# PCB_sch.net
KiCad netlist of a schematic drawn in EAGLE
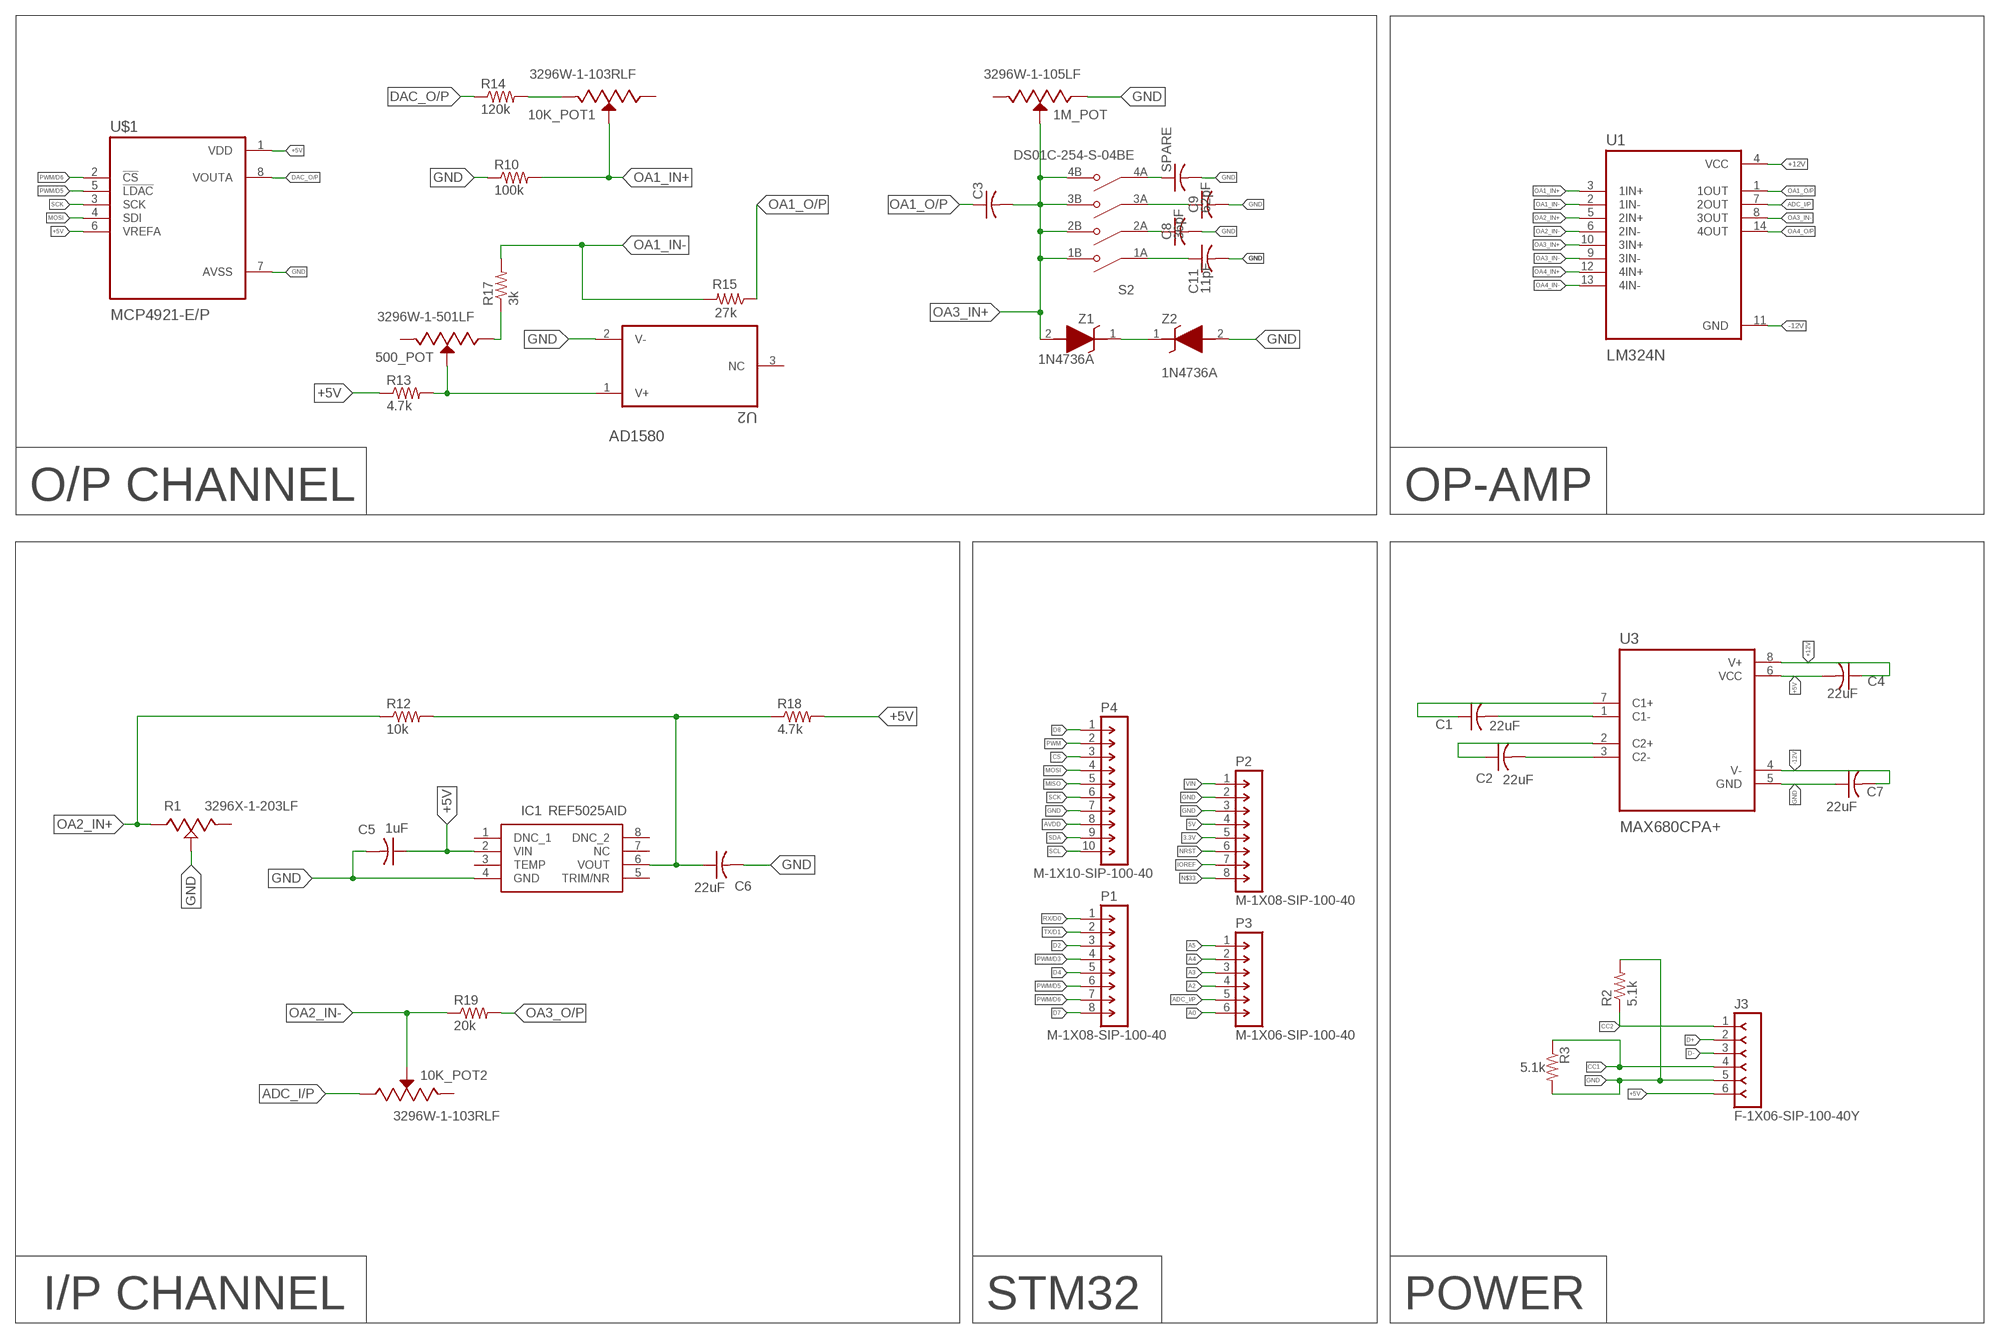
[diagram p0: schematic, sheet 1]

(export (version "E")
  (design (tool "Eeschema 10.0.6"))
  (components
    (comp (ref "1M_POT")
      (value "3296W-1-105LF")
      (footprint "eagle-import:TRIM_3296W-1-105LF")
      (fields (field (name "MF") "Bourns"))
      (libsource (lib "eagle-import") (part "3296W-1-105LF"))
    )
    (comp (ref "10K_POT1")
      (value "3296W-1-103RLF")
      (footprint "eagle-import:TRIM_3296W-1-103RLF")
      (fields (field (name "MF") "Bourns"))
      (libsource (lib "eagle-import") (part "3296W-1-103RLF"))
    )
    (comp (ref "10K_POT2")
      (value "3296W-1-103RLF")
      (footprint "eagle-import:TRIM_3296W-1-103RLF")
      (fields (field (name "MF") "Bourns"))
      (libsource (lib "eagle-import") (part "3296W-1-103RLF"))
    )
    (comp (ref "500_POT")
      (value "3296W-1-501LF")
      (footprint "eagle-import:TRIM_3296W-1-501LF")
      (fields (field (name "MF") "Bourns"))
      (libsource (lib "eagle-import") (part "3296W-1-501LF"))
    )
    (comp (ref "C1")
      (value "22uF")
      (footprint "eagle-import:C0805")
      (libsource (lib "eagle-import") (part "C-USC0805"))
    )
    (comp (ref "C2")
      (value "22uF")
      (footprint "eagle-import:C0805")
      (libsource (lib "eagle-import") (part "C-USC0805"))
    )
    (comp (ref "C3")
      (value "C-US050-030X075")
      (footprint "eagle-import:C050-030X075")
      (libsource (lib "eagle-import") (part "C-US050-030X075"))
    )
    (comp (ref "C4")
      (value "22uF")
      (footprint "eagle-import:C0805")
      (libsource (lib "eagle-import") (part "C-USC0805"))
    )
    (comp (ref "C5")
      (value "1uF")
      (footprint "eagle-import:C0805K")
      (libsource (lib "eagle-import") (part "C-USC0805K"))
    )
    (comp (ref "C6")
      (value "22uF")
      (footprint "eagle-import:C0805K")
      (libsource (lib "eagle-import") (part "C-USC0805K"))
    )
    (comp (ref "C7")
      (value "22uF")
      (footprint "eagle-import:C0805")
      (libsource (lib "eagle-import") (part "C-USC0805"))
    )
    (comp (ref "C8")
      (value "36pF")
      (footprint "eagle-import:C0805")
      (libsource (lib "eagle-import") (part "C-USC0805"))
    )
    (comp (ref "C9")
      (value "62pF")
      (footprint "eagle-import:C0805")
      (libsource (lib "eagle-import") (part "C-USC0805"))
    )
    (comp (ref "C11")
      (value "11pF")
      (footprint "eagle-import:C0805")
      (fields (field (name "SPICEPREFIX") "C"))
      (libsource (lib "eagle-import") (part "C-USC0805"))
    )
    (comp (ref "IC1")
      (value "REF5025AID")
      (footprint "eagle-import:SOIC127P600X175-8N")
      (fields (field (name "MOUSER_PART_NUMBER") "595-REF5025AID"))
      (libsource (lib "eagle-import") (part "REF5025AID"))
    )
    (comp (ref "J3")
      (value "F-1X06-SIP-100-40Y")
      (footprint "eagle-import:SIP-100-06-40Y")
      (libsource (lib "eagle-import") (part "F-1X06-SIP-100-40Y"))
    )
    (comp (ref "P1")
      (value "M-1X08-SIP-100-40")
      (footprint "eagle-import:SIP-100-08-40")
      (libsource (lib "eagle-import") (part "M-1X08-SIP-100-40"))
    )
    (comp (ref "P2")
      (value "M-1X08-SIP-100-40")
      (footprint "eagle-import:SIP-100-08-40")
      (libsource (lib "eagle-import") (part "M-1X08-SIP-100-40"))
    )
    (comp (ref "P3")
      (value "M-1X06-SIP-100-40")
      (footprint "eagle-import:SIP-100-06-40")
      (libsource (lib "eagle-import") (part "M-1X06-SIP-100-40"))
    )
    (comp (ref "P4")
      (value "M-1X10-SIP-100-40")
      (footprint "eagle-import:SIP-100-10-40")
      (libsource (lib "eagle-import") (part "M-1X10-SIP-100-40"))
    )
    (comp (ref "R1")
      (value "3296X-1-203LF")
      (footprint "eagle-import:TRIM_3296X-1-203LF")
      (fields (field (name "MF") "Bourns"))
      (libsource (lib "eagle-import") (part "3296X-1-203LF"))
    )
    (comp (ref "R2")
      (value "5.1k")
      (footprint "eagle-import:R0805")
      (libsource (lib "eagle-import") (part "R-US_R0805"))
    )
    (comp (ref "R3")
      (value "5.1k")
      (footprint "eagle-import:R0805")
      (libsource (lib "eagle-import") (part "R-US_R0805"))
    )
    (comp (ref "R10")
      (value "100k")
      (footprint "eagle-import:M0805")
      (libsource (lib "eagle-import") (part "R-US_M0805"))
    )
    (comp (ref "R12")
      (value "10k")
      (footprint "eagle-import:M0805")
      (libsource (lib "eagle-import") (part "R-US_M0805"))
    )
    (comp (ref "R13")
      (value "4.7k")
      (footprint "eagle-import:M0805")
      (libsource (lib "eagle-import") (part "R-US_M0805"))
    )
    (comp (ref "R14")
      (value "120k")
      (footprint "eagle-import:M0805")
      (libsource (lib "eagle-import") (part "R-US_M0805"))
    )
    (comp (ref "R15")
      (value "27k")
      (footprint "eagle-import:M0805")
      (libsource (lib "eagle-import") (part "R-US_M0805"))
    )
    (comp (ref "R17")
      (value "3k")
      (footprint "eagle-import:M0805")
      (libsource (lib "eagle-import") (part "R-US_M0805"))
    )
    (comp (ref "R18")
      (value "4.7k")
      (footprint "eagle-import:M0805")
      (libsource (lib "eagle-import") (part "R-US_M0805"))
    )
    (comp (ref "R19")
      (value "20k")
      (footprint "eagle-import:M0805")
      (libsource (lib "eagle-import") (part "R-US_M0805"))
    )
    (comp (ref "S2")
      (value "DS01C-254-S-04BE")
      (footprint "eagle-import:SW_DS01C-254-S-04BE")
      (fields (field (name "MANUFACTURER") "CUI"))
      (libsource (lib "eagle-import") (part "DS01C-254-S-04BE"))
    )
    (comp (ref "SPARE")
      (value "C-USC0805")
      (footprint "eagle-import:C0805")
      (libsource (lib "eagle-import") (part "C-USC0805"))
    )
    (comp (ref "U$1")
      (value "MCP4921-E/P")
      (footprint "eagle-import:DIP787W46P254L927H533Q8")
      (fields (field (name "MF") "Microchip"))
      (libsource (lib "eagle-import") (part "MCP4921-E/P"))
    )
    (comp (ref "U1")
      (value "LM324N")
      (footprint "eagle-import:DIP794W45P254L1969H508Q14")
      (fields (field (name "MF") "STMicroelectronics"))
      (libsource (lib "eagle-import") (part "LM324N"))
    )
    (comp (ref "U2")
      (value "AD1580")
      (footprint "eagle-import:SOT96P237X112-3N")
      (libsource (lib "eagle-import") (part "AD1580BRTZ-R2-REEL7"))
    )
    (comp (ref "U3")
      (value "MAX680CPA+")
      (footprint "eagle-import:DIP794W47P254L991H457Q8")
      (fields (field (name "MF") "Maxim Integrated Products"))
      (libsource (lib "eagle-import") (part "MAX680CPA+"))
    )
    (comp (ref "Z1")
      (value "1N4736A")
      (footprint "eagle-import:DIOAD1413W86L463D238")
      (fields (field (name "MOUSER_PART_NUMBER") "512-1N4736A"))
      (libsource (lib "eagle-import") (part "1N4736A"))
    )
    (comp (ref "Z2")
      (value "1N4736A")
      (footprint "eagle-import:DIOAD1413W86L463D238")
      (fields (field (name "MOUSER_PART_NUMBER") "512-1N4736A"))
      (libsource (lib "eagle-import") (part "1N4736A"))
    )
  )
  (nets
    (net (code "1") (name "+5V") (class "Default")
      (node (ref "C4") (pin "2") (pinfunction "2_2") (pintype "passive"))
      (node (ref "C5") (pin "1") (pinfunction "1_1") (pintype "passive"))
      (node (ref "IC1") (pin "2") (pinfunction "VIN_2") (pintype "bidirectional"))
      (node (ref "J3") (pin "6") (pinfunction "6_6") (pintype "passive"))
      (node (ref "R13") (pin "1") (pinfunction "1_1") (pintype "passive"))
      (node (ref "R18") (pin "2") (pinfunction "2_2") (pintype "passive"))
      (node (ref "U$1") (pin "1") (pinfunction "VDD_1") (pintype "power_in"))
      (node (ref "U$1") (pin "6") (pinfunction "VREFA_6") (pintype "input"))
      (node (ref "U3") (pin "6") (pinfunction "VCC_6") (pintype "power_in"))
    )
    (net (code "2") (name "+12V") (class "Default")
      (node (ref "C4") (pin "1") (pinfunction "1_1") (pintype "passive"))
      (node (ref "U1") (pin "4") (pinfunction "VCC_4") (pintype "power_in"))
      (node (ref "U3") (pin "8") (pinfunction "V+_8") (pintype "power_in"))
    )
    (net (code "3") (name "-12V") (class "Default")
      (node (ref "C7") (pin "2") (pinfunction "2_2") (pintype "passive"))
      (node (ref "U1") (pin "11") (pinfunction "GND_11") (pintype "power_in"))
      (node (ref "U3") (pin "4") (pinfunction "V-_4") (pintype "power_in"))
    )
    (net (code "4") (name "3.3V") (class "Default")
      (node (ref "P2") (pin "5") (pinfunction "5_5") (pintype "passive"))
    )
    (net (code "5") (name "5V") (class "Default")
      (node (ref "P2") (pin "4") (pinfunction "4_4") (pintype "passive"))
    )
    (net (code "6") (name "A0") (class "Default")
      (node (ref "P3") (pin "6") (pinfunction "6_6") (pintype "passive"))
    )
    (net (code "7") (name "A2") (class "Default")
      (node (ref "P3") (pin "4") (pinfunction "4_4") (pintype "passive"))
    )
    (net (code "8") (name "A3") (class "Default")
      (node (ref "P3") (pin "3") (pinfunction "3_3") (pintype "passive"))
    )
    (net (code "9") (name "A4") (class "Default")
      (node (ref "P3") (pin "2") (pinfunction "2_2") (pintype "passive"))
    )
    (net (code "10") (name "A5") (class "Default")
      (node (ref "P3") (pin "1") (pinfunction "1_1") (pintype "passive"))
    )
    (net (code "11") (name "ADC_I{slash}P") (class "Default")
      (node (ref "10K_POT2") (pin "1") (pinfunction "CCW_1") (pintype "passive"))
      (node (ref "P3") (pin "5") (pinfunction "5_5") (pintype "passive"))
      (node (ref "U1") (pin "7") (pinfunction "2OUT_7") (pintype "output"))
    )
    (net (code "12") (name "AVDD") (class "Default")
      (node (ref "P4") (pin "8") (pinfunction "8_8") (pintype "passive"))
    )
    (net (code "13") (name "CC1") (class "Default")
      (node (ref "J3") (pin "4") (pinfunction "4_4") (pintype "passive"))
      (node (ref "R3") (pin "1") (pinfunction "1_1") (pintype "passive"))
    )
    (net (code "14") (name "CC2") (class "Default")
      (node (ref "J3") (pin "1") (pinfunction "1_1") (pintype "passive"))
      (node (ref "R2") (pin "1") (pinfunction "1_1") (pintype "passive"))
    )
    (net (code "15") (name "CS") (class "Default")
      (node (ref "P4") (pin "3") (pinfunction "3_3") (pintype "passive"))
    )
    (net (code "16") (name "D+") (class "Default")
      (node (ref "J3") (pin "2") (pinfunction "2_2") (pintype "passive"))
    )
    (net (code "17") (name "D-") (class "Default")
      (node (ref "J3") (pin "3") (pinfunction "3_3") (pintype "passive"))
    )
    (net (code "18") (name "D2") (class "Default")
      (node (ref "P1") (pin "3") (pinfunction "3_3") (pintype "passive"))
    )
    (net (code "19") (name "D4") (class "Default")
      (node (ref "P1") (pin "5") (pinfunction "5_5") (pintype "passive"))
    )
    (net (code "20") (name "D7") (class "Default")
      (node (ref "P1") (pin "8") (pinfunction "8_8") (pintype "passive"))
    )
    (net (code "21") (name "D8") (class "Default")
      (node (ref "P4") (pin "1") (pinfunction "1_1") (pintype "passive"))
    )
    (net (code "22") (name "DAC_O{slash}P") (class "Default")
      (node (ref "R14") (pin "1") (pinfunction "1_1") (pintype "passive"))
      (node (ref "U$1") (pin "8") (pinfunction "VOUTA_8") (pintype "output"))
    )
    (net (code "23") (name "GND") (class "Default")
      (node (ref "1M_POT") (pin "1") (pinfunction "CCW_1") (pintype "passive"))
      (node (ref "C11") (pin "2") (pinfunction "2_2") (pintype "passive"))
      (node (ref "C5") (pin "2") (pinfunction "2_2") (pintype "passive"))
      (node (ref "C6") (pin "2") (pinfunction "2_2") (pintype "passive"))
      (node (ref "C7") (pin "1") (pinfunction "1_1") (pintype "passive"))
      (node (ref "C8") (pin "2") (pinfunction "2_2") (pintype "passive"))
      (node (ref "C9") (pin "2") (pinfunction "2_2") (pintype "passive"))
      (node (ref "IC1") (pin "4") (pinfunction "GND_4") (pintype "bidirectional"))
      (node (ref "J3") (pin "5") (pinfunction "5_5") (pintype "passive"))
      (node (ref "P2") (pin "2") (pinfunction "2_2") (pintype "passive"))
      (node (ref "P2") (pin "3") (pinfunction "3_3") (pintype "passive"))
      (node (ref "P4") (pin "7") (pinfunction "7_7") (pintype "passive"))
      (node (ref "R1") (pin "2") (pinfunction "WIPER_2") (pintype "passive"))
      (node (ref "R10") (pin "1") (pinfunction "1_1") (pintype "passive"))
      (node (ref "R2") (pin "2") (pinfunction "2_2") (pintype "passive"))
      (node (ref "R3") (pin "2") (pinfunction "2_2") (pintype "passive"))
      (node (ref "SPARE") (pin "2") (pinfunction "2_2") (pintype "passive"))
      (node (ref "U$1") (pin "7") (pinfunction "AVSS_7") (pintype "power_in"))
      (node (ref "U2") (pin "2") (pinfunction "V-_2") (pintype "power_in"))
      (node (ref "U3") (pin "5") (pinfunction "GND_5") (pintype "power_in"))
      (node (ref "Z2") (pin "2") (pinfunction "A_2") (pintype "bidirectional"))
    )
    (net (code "24") (name "IOREF") (class "Default")
      (node (ref "P2") (pin "7") (pinfunction "7_7") (pintype "passive"))
    )
    (net (code "25") (name "MISO") (class "Default")
      (node (ref "P4") (pin "5") (pinfunction "5_5") (pintype "passive"))
    )
    (net (code "26") (name "MOSI") (class "Default")
      (node (ref "P4") (pin "4") (pinfunction "4_4") (pintype "passive"))
      (node (ref "U$1") (pin "4") (pinfunction "SDI_4") (pintype "input"))
    )
    (net (code "27") (name "N$33") (class "Default")
      (node (ref "P2") (pin "8") (pinfunction "8_8") (pintype "passive"))
    )
    (net (code "28") (name "NRST") (class "Default")
      (node (ref "P2") (pin "6") (pinfunction "6_6") (pintype "passive"))
    )
    (net (code "29") (name "Net-(10K_POT1-CW)") (class "Default")
      (node (ref "10K_POT1") (pin "3") (pinfunction "CW_3") (pintype "passive"))
      (node (ref "R14") (pin "2") (pinfunction "2_2") (pintype "passive"))
    )
    (net (code "30") (name "Net-(10K_POT1-WIPER)") (class "Default")
      (node (ref "10K_POT1") (pin "2") (pinfunction "WIPER_2") (pintype "passive"))
      (node (ref "R10") (pin "2") (pinfunction "2_2") (pintype "passive"))
    )
    (net (code "31") (name "Net-(500_POT-CCW)") (class "Default")
      (node (ref "500_POT") (pin "1") (pinfunction "CCW_1") (pintype "passive"))
      (node (ref "R17") (pin "1") (pinfunction "1_1") (pintype "passive"))
    )
    (net (code "32") (name "Net-(500_POT-WIPER)") (class "Default")
      (node (ref "500_POT") (pin "2") (pinfunction "WIPER_2") (pintype "passive"))
      (node (ref "R13") (pin "2") (pinfunction "2_2") (pintype "passive"))
      (node (ref "U2") (pin "1") (pinfunction "V+_1") (pintype "power_in"))
    )
    (net (code "33") (name "Net-(IC1-VOUT)") (class "Default")
      (node (ref "C6") (pin "1") (pinfunction "1_1") (pintype "passive"))
      (node (ref "IC1") (pin "6") (pinfunction "VOUT_6") (pintype "bidirectional"))
      (node (ref "R12") (pin "2") (pinfunction "2_2") (pintype "passive"))
      (node (ref "R18") (pin "1") (pinfunction "1_1") (pintype "passive"))
    )
    (net (code "34") (name "Net-(R15-Pad2)") (class "Default")
      (node (ref "R15") (pin "2") (pinfunction "2_2") (pintype "passive"))
      (node (ref "R17") (pin "2") (pinfunction "2_2") (pintype "passive"))
    )
    (net (code "35") (name "Net-(S2-COM1)") (class "Default")
      (node (ref "C11") (pin "1") (pinfunction "1_1") (pintype "passive"))
      (node (ref "S2") (pin "1A") (pinfunction "COM1_1A") (pintype "passive"))
    )
    (net (code "36") (name "Net-(S2-COM2)") (class "Default")
      (node (ref "C8") (pin "1") (pinfunction "1_1") (pintype "passive"))
      (node (ref "S2") (pin "2A") (pinfunction "COM2_2A") (pintype "passive"))
    )
    (net (code "37") (name "Net-(S2-COM3)") (class "Default")
      (node (ref "C9") (pin "1") (pinfunction "1_1") (pintype "passive"))
      (node (ref "S2") (pin "3A") (pinfunction "COM3_3A") (pintype "passive"))
    )
    (net (code "38") (name "Net-(S2-COM4)") (class "Default")
      (node (ref "S2") (pin "4A") (pinfunction "COM4_4A") (pintype "passive"))
      (node (ref "SPARE") (pin "1") (pinfunction "1_1") (pintype "passive"))
    )
    (net (code "39") (name "Net-(U3-C1+)") (class "Default")
      (node (ref "C1") (pin "1") (pinfunction "1_1") (pintype "passive"))
      (node (ref "U3") (pin "7") (pinfunction "C1+_7") (pintype "passive"))
    )
    (net (code "40") (name "Net-(U3-C1-)") (class "Default")
      (node (ref "C1") (pin "2") (pinfunction "2_2") (pintype "passive"))
      (node (ref "U3") (pin "1") (pinfunction "C1-_1") (pintype "passive"))
    )
    (net (code "41") (name "Net-(U3-C2+)") (class "Default")
      (node (ref "C2") (pin "1") (pinfunction "1_1") (pintype "passive"))
      (node (ref "U3") (pin "2") (pinfunction "C2+_2") (pintype "passive"))
    )
    (net (code "42") (name "Net-(U3-C2-)") (class "Default")
      (node (ref "C2") (pin "2") (pinfunction "2_2") (pintype "passive"))
      (node (ref "U3") (pin "3") (pinfunction "C2-_3") (pintype "passive"))
    )
    (net (code "43") (name "Net-(Z1-K)") (class "Default")
      (node (ref "Z1") (pin "1") (pinfunction "K_1") (pintype "bidirectional"))
      (node (ref "Z2") (pin "1") (pinfunction "K_1") (pintype "bidirectional"))
    )
    (net (code "44") (name "OA1_IN+") (class "Default")
      (node (ref "U1") (pin "3") (pinfunction "1IN+_3") (pintype "input"))
    )
    (net (code "45") (name "OA1_IN-") (class "Default")
      (node (ref "U1") (pin "2") (pinfunction "1IN-_2") (pintype "input"))
    )
    (net (code "46") (name "OA1_O{slash}P") (class "Default")
      (node (ref "C3") (pin "1") (pinfunction "1_1") (pintype "passive"))
      (node (ref "R15") (pin "1") (pinfunction "1_1") (pintype "passive"))
      (node (ref "U1") (pin "1") (pinfunction "1OUT_1") (pintype "output"))
    )
    (net (code "47") (name "OA2_IN+") (class "Default")
      (node (ref "R1") (pin "1") (pinfunction "CCW_1") (pintype "passive"))
      (node (ref "R12") (pin "1") (pinfunction "1_1") (pintype "passive"))
      (node (ref "U1") (pin "5") (pinfunction "2IN+_5") (pintype "input"))
    )
    (net (code "48") (name "OA2_IN-") (class "Default")
      (node (ref "10K_POT2") (pin "2") (pinfunction "WIPER_2") (pintype "passive"))
      (node (ref "R19") (pin "1") (pinfunction "1_1") (pintype "passive"))
      (node (ref "U1") (pin "6") (pinfunction "2IN-_6") (pintype "input"))
    )
    (net (code "49") (name "OA3_IN+") (class "Default")
      (node (ref "1M_POT") (pin "2") (pinfunction "WIPER_2") (pintype "passive"))
      (node (ref "C3") (pin "2") (pinfunction "2_2") (pintype "passive"))
      (node (ref "S2") (pin "1B") (pinfunction "NO1_1B") (pintype "passive"))
      (node (ref "S2") (pin "2B") (pinfunction "NO2_2B") (pintype "passive"))
      (node (ref "S2") (pin "3B") (pinfunction "NO3_3B") (pintype "passive"))
      (node (ref "S2") (pin "4B") (pinfunction "NO4_4B") (pintype "passive"))
      (node (ref "U1") (pin "10") (pinfunction "3IN+_10") (pintype "input"))
      (node (ref "Z1") (pin "2") (pinfunction "A_2") (pintype "bidirectional"))
    )
    (net (code "50") (name "OA3_IN-") (class "Default")
      (node (ref "U1") (pin "8") (pinfunction "3OUT_8") (pintype "output"))
      (node (ref "U1") (pin "9") (pinfunction "3IN-_9") (pintype "input"))
    )
    (net (code "51") (name "OA3_O{slash}P") (class "Default")
      (node (ref "R19") (pin "2") (pinfunction "2_2") (pintype "passive"))
    )
    (net (code "52") (name "OA4_IN+") (class "Default")
      (node (ref "U1") (pin "12") (pinfunction "4IN+_12") (pintype "input"))
    )
    (net (code "53") (name "OA4_IN-") (class "Default")
      (node (ref "U1") (pin "13") (pinfunction "4IN-_13") (pintype "input"))
    )
    (net (code "54") (name "OA4_O{slash}P") (class "Default")
      (node (ref "U1") (pin "14") (pinfunction "4OUT_14") (pintype "output"))
    )
    (net (code "55") (name "PWM") (class "Default")
      (node (ref "P4") (pin "2") (pinfunction "2_2") (pintype "passive"))
    )
    (net (code "56") (name "PWM{slash}D3") (class "Default")
      (node (ref "P1") (pin "4") (pinfunction "4_4") (pintype "passive"))
    )
    (net (code "57") (name "PWM{slash}D5") (class "Default")
      (node (ref "P1") (pin "6") (pinfunction "6_6") (pintype "passive"))
      (node (ref "U$1") (pin "5") (pinfunction "~{LDAC}_5") (pintype "input"))
    )
    (net (code "58") (name "PWM{slash}D6") (class "Default")
      (node (ref "P1") (pin "7") (pinfunction "7_7") (pintype "passive"))
      (node (ref "U$1") (pin "2") (pinfunction "~{CS}_2") (pintype "input"))
    )
    (net (code "59") (name "RX{slash}D0") (class "Default")
      (node (ref "P1") (pin "1") (pinfunction "1_1") (pintype "passive"))
    )
    (net (code "60") (name "SCK") (class "Default")
      (node (ref "P4") (pin "6") (pinfunction "6_6") (pintype "passive"))
      (node (ref "U$1") (pin "3") (pinfunction "SCK_3") (pintype "input"))
    )
    (net (code "61") (name "SCL") (class "Default")
      (node (ref "P4") (pin "10") (pinfunction "10_10") (pintype "passive"))
    )
    (net (code "62") (name "SDA") (class "Default")
      (node (ref "P4") (pin "9") (pinfunction "9_9") (pintype "passive"))
    )
    (net (code "63") (name "TX{slash}D1") (class "Default")
      (node (ref "P1") (pin "2") (pinfunction "2_2") (pintype "passive"))
    )
    (net (code "64") (name "VIN") (class "Default")
      (node (ref "P2") (pin "1") (pinfunction "1_1") (pintype "passive"))
    )
    (net (code "65") (name "unconnected-(1M_POT-CW-Pad3)") (class "Default")
      (node (ref "1M_POT") (pin "3") (pinfunction "CW_3") (pintype "passive"))
    )
    (net (code "66") (name "unconnected-(10K_POT1-CCW-Pad1)") (class "Default")
      (node (ref "10K_POT1") (pin "1") (pinfunction "CCW_1") (pintype "passive"))
    )
    (net (code "67") (name "unconnected-(10K_POT2-CW-Pad3)") (class "Default")
      (node (ref "10K_POT2") (pin "3") (pinfunction "CW_3") (pintype "passive"))
    )
    (net (code "68") (name "unconnected-(500_POT-CW-Pad3)") (class "Default")
      (node (ref "500_POT") (pin "3") (pinfunction "CW_3") (pintype "passive"))
    )
    (net (code "69") (name "unconnected-(IC1-DNC_1-Pad1)") (class "Default")
      (node (ref "IC1") (pin "1") (pinfunction "DNC_1_1") (pintype "bidirectional"))
    )
    (net (code "70") (name "unconnected-(IC1-DNC_2-Pad8)") (class "Default")
      (node (ref "IC1") (pin "8") (pinfunction "DNC_2_8") (pintype "bidirectional"))
    )
    (net (code "71") (name "unconnected-(IC1-NC-Pad7)") (class "Default")
      (node (ref "IC1") (pin "7") (pinfunction "NC_7") (pintype "no_connect"))
    )
    (net (code "72") (name "unconnected-(IC1-TEMP-Pad3)") (class "Default")
      (node (ref "IC1") (pin "3") (pinfunction "TEMP_3") (pintype "bidirectional"))
    )
    (net (code "73") (name "unconnected-(IC1-TRIM{slash}NR-Pad5)") (class "Default")
      (node (ref "IC1") (pin "5") (pinfunction "TRIM/NR_5") (pintype "bidirectional"))
    )
    (net (code "74") (name "unconnected-(R1-CW-Pad3)") (class "Default")
      (node (ref "R1") (pin "3") (pinfunction "CW_3") (pintype "passive"))
    )
    (net (code "75") (name "unconnected-(U2-NC-Pad3)") (class "Default")
      (node (ref "U2") (pin "3") (pinfunction "NC_3") (pintype "bidirectional"))
    )
  )
)
